# WPT_Round_2_1_RX_Schematics.net
KiCad netlist of a schematic drawn in Altium Designer
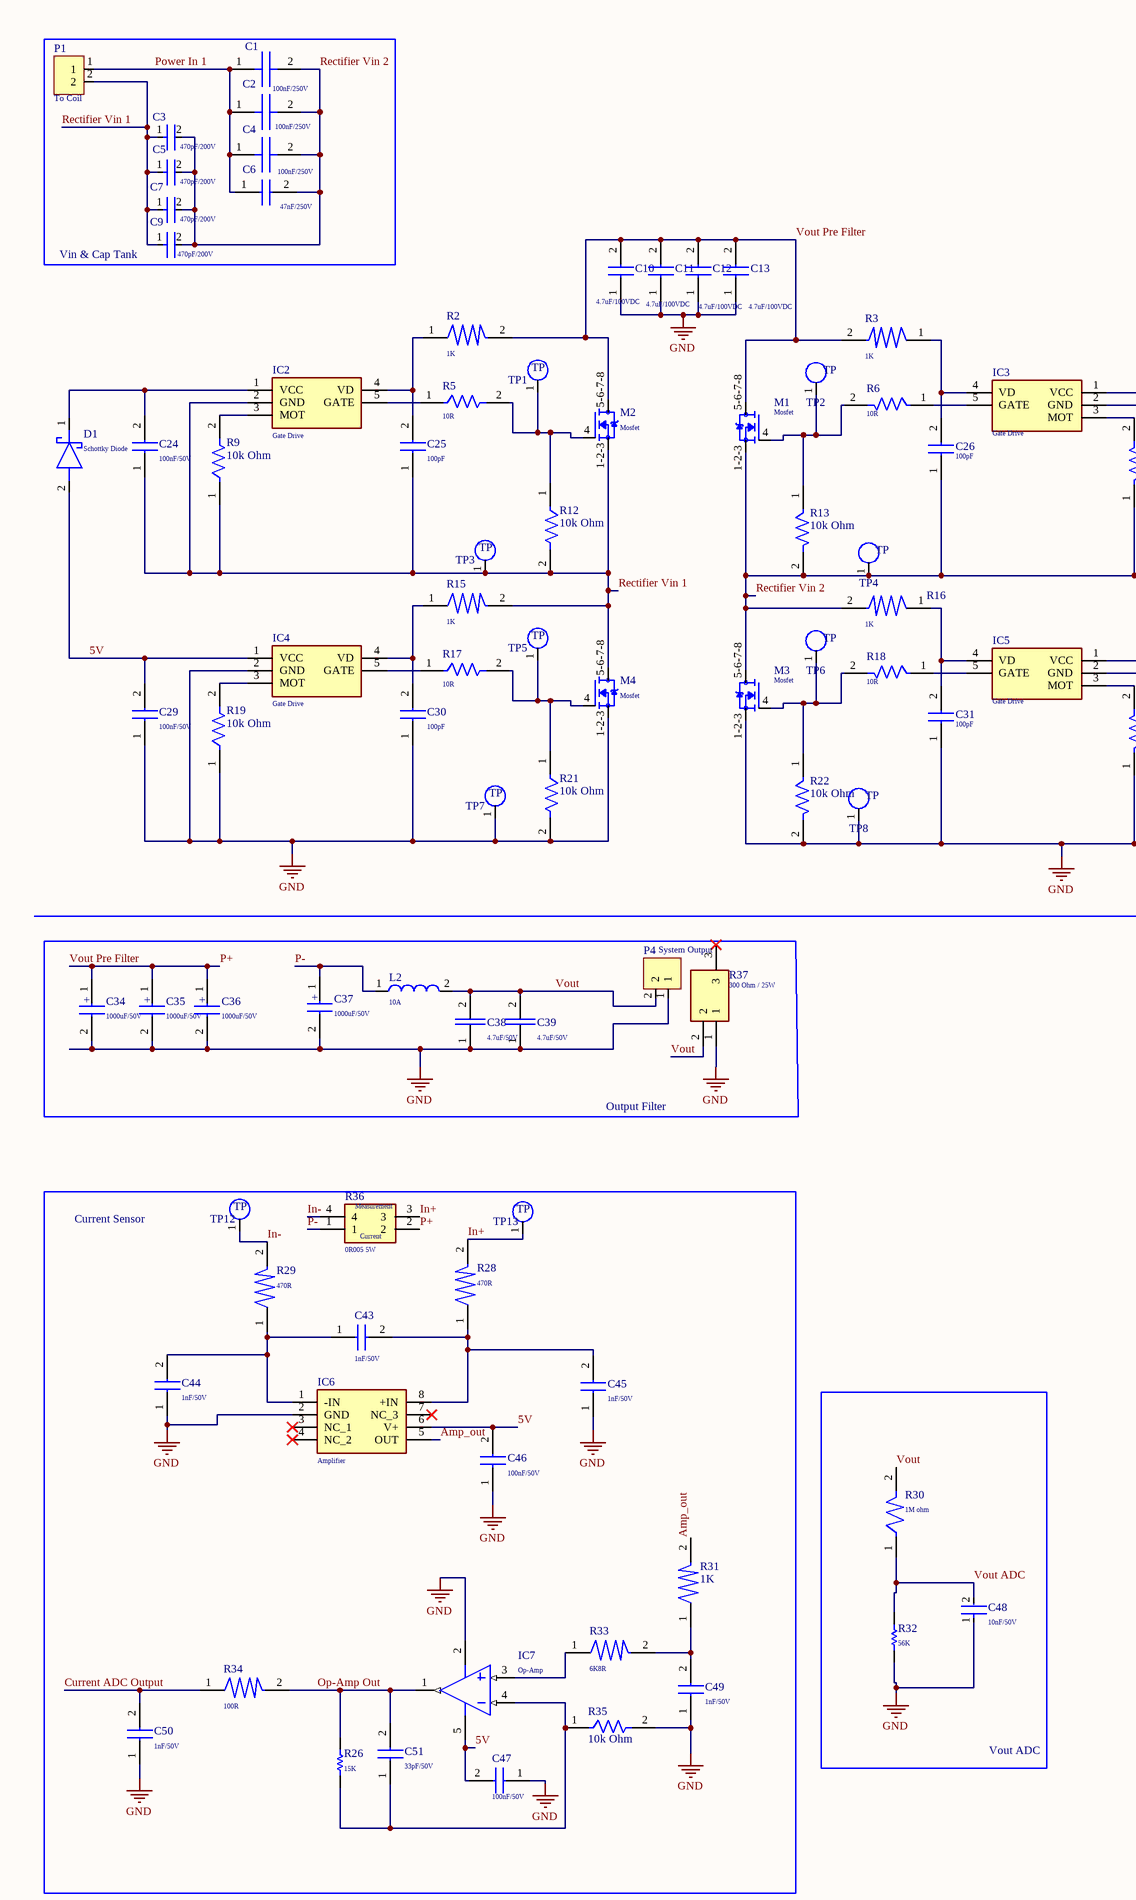
[diagram p0: WPT Round 2.1 RX Schematics.SchDoc, left]
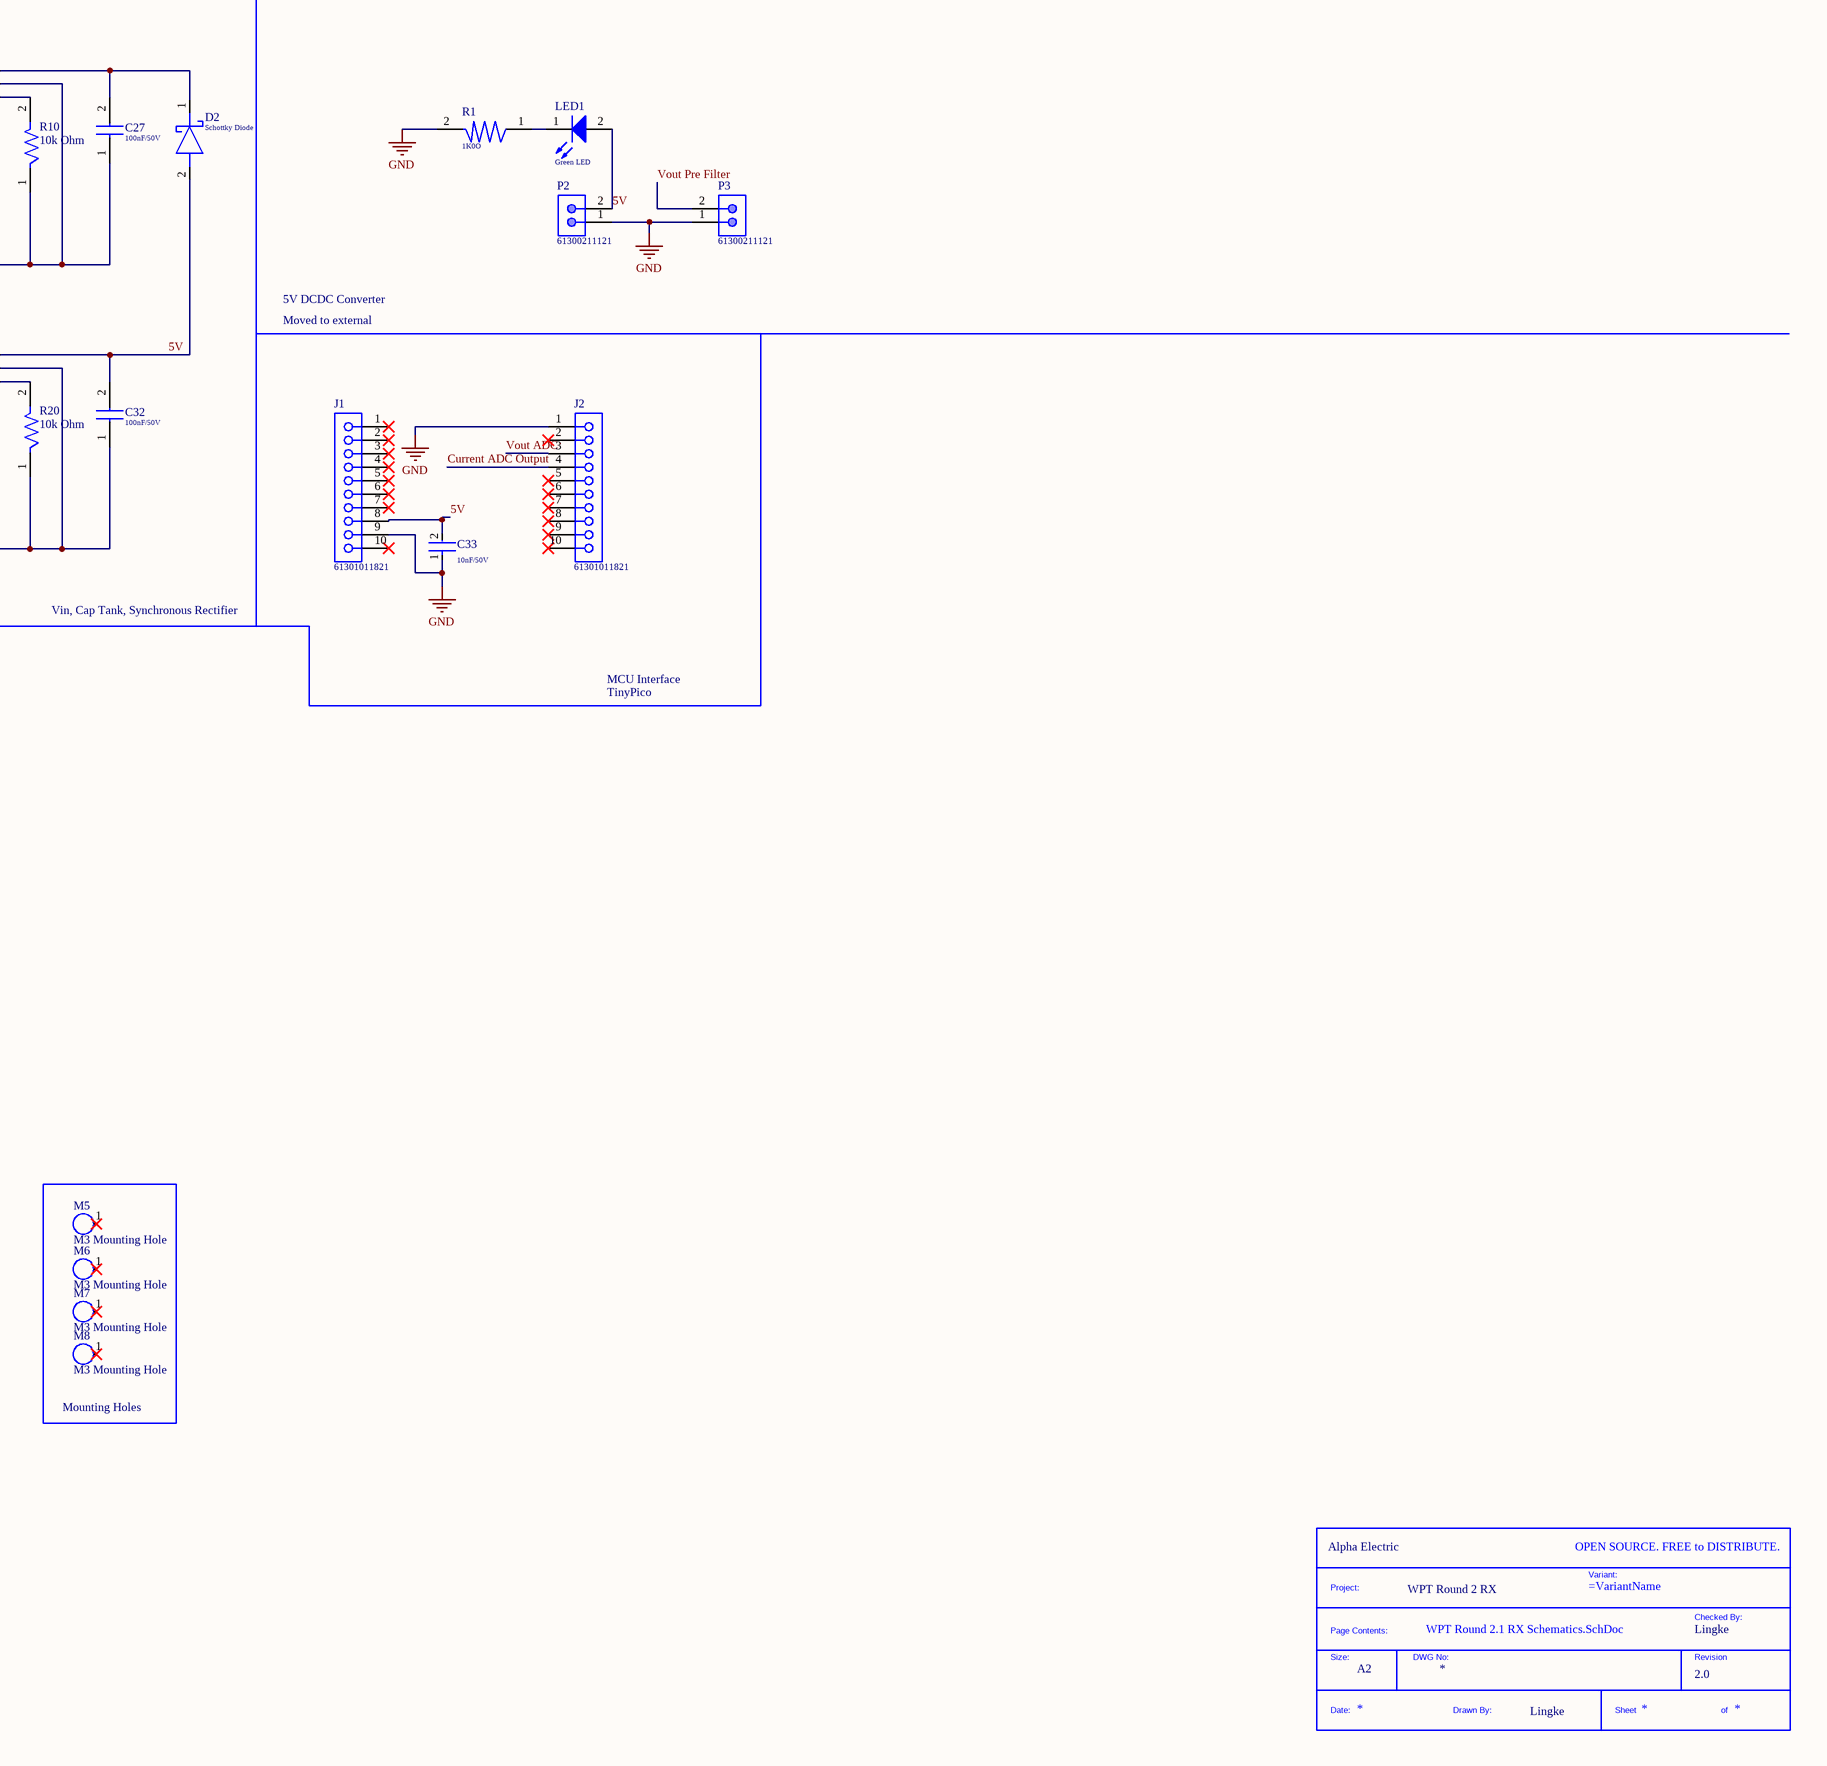
[diagram p1: WPT Round 2.1 RX Schematics.SchDoc, right]

(export (version "E")
  (design (tool "Eeschema 10.0.6"))
  (components
    (comp (ref "*")
      (value "Title_Block")
      (description "Standard Title Block.")
      (fields
        (field (name "PROJECT NAME") "WPT Round 2 RX")
        (field (name "COMPANY") "Alpha Electric")
        (field (name "DRAWN BY") "Lingke")
        (field (name "REVISION") "2.0")
        (field (name "DWG NO") "*")
        (field (name "SIZE") "A2")
        (field (name "CHECKED BY") "Lingke")
      )
      (libsource (lib "Symbol Library") (part "Title_Block"))
    )
    (comp (ref "C1")
      (value "100nF/250V")
      (footprint "SamacSys:CAPC4532X220N")
      (fields (field (name "MANUFACTURER_PART_NUMBER") "C1812C104JAGACAUTO"))
      (libsource (lib "Symbol Library") (part "C1812C104JAGACAUTO"))
    )
    (comp (ref "C2")
      (value "100nF/250V")
      (footprint "SamacSys:CAPC4532X220N")
      (fields (field (name "MANUFACTURER_PART_NUMBER") "C1812C104JAGACAUTO"))
      (libsource (lib "Symbol Library") (part "C1812C104JAGACAUTO"))
    )
    (comp (ref "C3")
      (value "470pF/200V")
      (footprint "FP-C1206C-EB-MFG")
      (description "CAP CER 470PF 200V 10% NP0 1206")
      (fields
        (field (name "OCTOPART") "https://octopart.com/c1206c471k2gactu-kemet-3658280")
        (field (name "TOLERANCE") "0.1")
      )
      (libsource (lib "Symbol Library") (part "C1206C471K2GACTU"))
    )
    (comp (ref "C4")
      (value "100nF/250V")
      (footprint "SamacSys:CAPC4532X220N")
      (fields (field (name "MANUFACTURER_PART_NUMBER") "C1812C104JAGACAUTO"))
      (libsource (lib "Symbol Library") (part "C1812C104JAGACAUTO"))
    )
    (comp (ref "C5")
      (value "470pF/200V")
      (footprint "FP-C1206C-EB-MFG")
      (description "CAP CER 470PF 200V 10% NP0 1206")
      (fields
        (field (name "OCTOPART") "https://octopart.com/c1206c471k2gactu-kemet-3658280")
        (field (name "TOLERANCE") "0.1")
      )
      (libsource (lib "Symbol Library") (part "C1206C471K2GACTU"))
    )
    (comp (ref "C6")
      (value "47nF/250V")
      (footprint "SamacSys:CAPC4532X350N")
      (description "Capacitor\r\n47nF/250V \r\nC0G")
      (fields (field (name "MANUFACTURER_PART_NUMBER") "C4532C0G2E473J320KA"))
      (libsource (lib "Symbol Library") (part "C4532C0G2E473J320KA"))
    )
    (comp (ref "C7")
      (value "470pF/200V")
      (footprint "FP-C1206C-EB-MFG")
      (description "CAP CER 470PF 200V 10% NP0 1206")
      (fields
        (field (name "OCTOPART") "https://octopart.com/c1206c471k2gactu-kemet-3658280")
        (field (name "TOLERANCE") "0.1")
      )
      (libsource (lib "Symbol Library") (part "C1206C471K2GACTU"))
    )
    (comp (ref "C9")
      (value "470pF/200V")
      (footprint "FP-C1206C-EB-MFG")
      (description "CAP CER 470PF 200V 10% NP0 1206")
      (fields
        (field (name "OCTOPART") "https://octopart.com/c1206c471k2gactu-kemet-3658280")
        (field (name "TOLERANCE") "0.1")
      )
      (libsource (lib "Symbol Library") (part "C1206C471K2GACTU"))
    )
    (comp (ref "C10")
      (value "4.7uF/100VDC")
      (footprint "SamacSys:CAPC3225X280N")
      (fields
        (field (name "MOUSER2 PART NUMBER") "810-CNC6P1X7R2A475K2")
        (field (name "MANUFACTURER_PART_NUMBER") "CNC6P1X7R2A475K250AE")
      )
      (libsource (lib "Symbol Library") (part "CNC6P1X7R2A475K250AE"))
    )
    (comp (ref "C11")
      (value "4.7uF/100VDC")
      (footprint "SamacSys:CAPC3225X280N")
      (fields
        (field (name "MOUSER2 PART NUMBER") "810-CNC6P1X7R2A475K2")
        (field (name "MANUFACTURER_PART_NUMBER") "CNC6P1X7R2A475K250AE")
      )
      (libsource (lib "Symbol Library") (part "CNC6P1X7R2A475K250AE"))
    )
    (comp (ref "C12")
      (value "4.7uF/100VDC")
      (footprint "SamacSys:CAPC3225X280N")
      (fields
        (field (name "MOUSER2 PART NUMBER") "810-CNC6P1X7R2A475K2")
        (field (name "MANUFACTURER_PART_NUMBER") "CNC6P1X7R2A475K250AE")
      )
      (libsource (lib "Symbol Library") (part "CNC6P1X7R2A475K250AE"))
    )
    (comp (ref "C13")
      (value "4.7uF/100VDC")
      (footprint "SamacSys:CAPC3225X280N")
      (fields
        (field (name "MOUSER2 PART NUMBER") "810-CNC6P1X7R2A475K2")
        (field (name "MANUFACTURER_PART_NUMBER") "CNC6P1X7R2A475K250AE")
      )
      (libsource (lib "Symbol Library") (part "CNC6P1X7R2A475K250AE"))
    )
    (comp (ref "C24")
      (value "100nF/50V")
      (footprint "SamacSys:CAPC2012X90N")
      (description "Capacitor 100nF/50V")
      (fields
        (field (name "MOUSER2 PART NUMBER") "710-885012207098")
        (field (name "MANUFACTURER_PART_NUMBER") "885012207098")
      )
      (libsource (lib "") (part "885012207098_1"))
    )
    (comp (ref "C25")
      (value "100pF")
      (footprint "SamacSys:CAPC2012X70N")
      (description "Capacitor 100pF")
      (fields (field (name "MANUFACTURER_PART_NUMBER") "885012007057"))
      (libsource (lib "") (part "885012007057_1"))
    )
    (comp (ref "C26")
      (value "100pF")
      (footprint "SamacSys:CAPC2012X70N")
      (description "Capacitor 100pF")
      (fields (field (name "MANUFACTURER_PART_NUMBER") "885012007057"))
      (libsource (lib "") (part "885012007057_1"))
    )
    (comp (ref "C27")
      (value "100nF/50V")
      (footprint "SamacSys:CAPC2012X90N")
      (description "Capacitor 100nF/50V")
      (fields
        (field (name "MOUSER2 PART NUMBER") "710-885012207098")
        (field (name "MANUFACTURER_PART_NUMBER") "885012207098")
      )
      (libsource (lib "") (part "885012207098_1"))
    )
    (comp (ref "C29")
      (value "100nF/50V")
      (footprint "SamacSys:CAPC2012X90N")
      (description "Capacitor 100nF/50V")
      (fields
        (field (name "MOUSER2 PART NUMBER") "710-885012207098")
        (field (name "MANUFACTURER_PART_NUMBER") "885012207098")
      )
      (libsource (lib "") (part "885012207098_2"))
    )
    (comp (ref "C30")
      (value "100pF")
      (footprint "SamacSys:CAPC2012X70N")
      (description "Capacitor 100pF")
      (fields (field (name "MANUFACTURER_PART_NUMBER") "885012007057"))
      (libsource (lib "Symbol Library") (part "885012007057"))
    )
    (comp (ref "C31")
      (value "100pF")
      (footprint "SamacSys:CAPC2012X70N")
      (description "Capacitor 100pF")
      (fields (field (name "MANUFACTURER_PART_NUMBER") "885012007057"))
      (libsource (lib "Symbol Library") (part "885012007057"))
    )
    (comp (ref "C32")
      (value "100nF/50V")
      (footprint "SamacSys:CAPC2012X90N")
      (description "Capacitor 100nF/50V")
      (fields
        (field (name "MOUSER2 PART NUMBER") "710-885012207098")
        (field (name "MANUFACTURER_PART_NUMBER") "885012207098")
      )
      (libsource (lib "") (part "885012207098_2"))
    )
    (comp (ref "C33")
      (value "10nF/50V")
      (footprint "0805 Capacitor")
      (libsource (lib "Symbol Library") (part "885012207092"))
    )
    (comp (ref "C34")
      (value "1000uF/50V")
      (footprint "SamacSys:CAPPRD500W62D1300H2650")
      (description "Capacitor 1000uF")
      (libsource (lib "Symbol Library") (part "ESH108M050AL4AA"))
    )
    (comp (ref "C35")
      (value "1000uF/50V")
      (footprint "SamacSys:CAPPRD500W62D1300H2650")
      (description "Capacitor 1000uF")
      (libsource (lib "Symbol Library") (part "ESH108M050AL4AA"))
    )
    (comp (ref "C36")
      (value "1000uF/50V")
      (footprint "SamacSys:CAPPRD500W62D1300H2650")
      (description "Capacitor 1000uF")
      (libsource (lib "Symbol Library") (part "ESH108M050AL4AA"))
    )
    (comp (ref "C37")
      (value "1000uF/50V")
      (footprint "SamacSys:CAPPRD500W62D1300H2650")
      (description "Capacitor 1000uF")
      (libsource (lib "Symbol Library") (part "ESH108M050AL4AA"))
    )
    (comp (ref "C38")
      (value "4.7uF/50V")
      (footprint "SamacSys:CAPC3225X280N")
      (description "Capacitor 4.7uF/50V")
      (fields (field (name "MANUFACTURER_PART_NUMBER") "885012209048"))
      (libsource (lib "Symbol Library") (part "885012209048"))
    )
    (comp (ref "C39")
      (value "4.7uF/50V")
      (footprint "SamacSys:CAPC3225X280N")
      (description "Capacitor 4.7uF/50V")
      (fields (field (name "MANUFACTURER_PART_NUMBER") "885012209048"))
      (libsource (lib "Symbol Library") (part "885012209048"))
    )
    (comp (ref "C43")
      (value "1nF/50V")
      (footprint "SamacSys:CAPC2012X90N")
      (fields (field (name "MANUFACTURER_PART_NUMBER") "885012207086"))
      (libsource (lib "Symbol Library") (part "885012207086"))
    )
    (comp (ref "C44")
      (value "1nF/50V")
      (footprint "SamacSys:CAPC2012X90N")
      (fields (field (name "MANUFACTURER_PART_NUMBER") "885012207086"))
      (libsource (lib "Symbol Library") (part "885012207086"))
    )
    (comp (ref "C45")
      (value "1nF/50V")
      (footprint "SamacSys:CAPC2012X90N")
      (fields (field (name "MANUFACTURER_PART_NUMBER") "885012207086"))
      (libsource (lib "Symbol Library") (part "885012207086"))
    )
    (comp (ref "C46")
      (value "100nF/50V")
      (footprint "SamacSys:CAPC2012X90N")
      (libsource (lib "Symbol Library") (part "885012207098"))
    )
    (comp (ref "C47")
      (value "100nF/50V")
      (footprint "SamacSys:CAPC2012X90N")
      (libsource (lib "Symbol Library") (part "885012207098"))
    )
    (comp (ref "C48")
      (value "10nF/50V")
      (footprint "0805 Capacitor")
      (libsource (lib "Symbol Library") (part "885012207092"))
    )
    (comp (ref "C49")
      (value "1nF/50V")
      (footprint "SamacSys:CAPC2012X90N")
      (fields (field (name "MANUFACTURER_PART_NUMBER") "885012207086"))
      (libsource (lib "Symbol Library") (part "885012207086"))
    )
    (comp (ref "C50")
      (value "1nF/50V")
      (footprint "SamacSys:CAPC2012X90N")
      (fields (field (name "MANUFACTURER_PART_NUMBER") "885012207086"))
      (libsource (lib "Symbol Library") (part "885012207086"))
    )
    (comp (ref "C51")
      (value "33pF/50V")
      (footprint "CAPC2012X90N")
      (description "Capacitor 33pF/50V")
      (fields (field (name "MANUFACTURER_PART_NUMBER") "C0805C330J5GACTU"))
      (libsource (lib "Symbol Library") (part "C0805C330J5GACTU"))
    )
    (comp (ref "D1")
      (value "Schottky Diode")
      (footprint "SamacSys:RB400VAM50TR")
      (fields
        (field (name "MOUSER2 PART NUMBER") "755-RB400VAM-50TR")
        (field (name "MANUFACTURER_PART_NUMBER") "RB400VAM-50TR")
      )
      (libsource (lib "Symbol Library") (part "RB400VAM-50TR"))
    )
    (comp (ref "D2")
      (value "Schottky Diode")
      (footprint "SamacSys:RB400VAM50TR")
      (fields
        (field (name "MOUSER2 PART NUMBER") "755-RB400VAM-50TR")
        (field (name "MANUFACTURER_PART_NUMBER") "RB400VAM-50TR")
      )
      (libsource (lib "Symbol Library") (part "RB400VAM-50TR"))
    )
    (comp (ref "IC2")
      (value "Gate Drive")
      (footprint "SamacSys:SOT95P280X145-5N")
      (description "Gate Driver IC")
      (fields (field (name "MANUFACTURER_PART_NUMBER") "IR1161LTRPBF"))
      (libsource (lib "") (part "IR1161LTRPBF_1"))
    )
    (comp (ref "IC3")
      (value "Gate Drive")
      (footprint "SamacSys:SOT95P280X145-5N")
      (description "Gate Driver IC")
      (fields (field (name "MANUFACTURER_PART_NUMBER") "IR1161LTRPBF"))
      (libsource (lib "Symbol Library") (part "IR1161LTRPBF"))
    )
    (comp (ref "IC4")
      (value "Gate Drive")
      (footprint "SamacSys:SOT95P280X145-5N")
      (description "Gate Driver IC")
      (fields (field (name "MANUFACTURER_PART_NUMBER") "IR1161LTRPBF"))
      (libsource (lib "") (part "IR1161LTRPBF_1"))
    )
    (comp (ref "IC5")
      (value "Gate Drive")
      (footprint "SamacSys:SOT95P280X145-5N")
      (description "Gate Driver IC")
      (fields (field (name "MANUFACTURER_PART_NUMBER") "IR1161LTRPBF"))
      (libsource (lib "Symbol Library") (part "IR1161LTRPBF"))
    )
    (comp (ref "IC6")
      (value "Amplifier")
      (footprint "SamacSys:SOIC127P600X175-8N")
      (description "Integrated Circuit Amplifier")
      (fields (field (name "MANUFACTURER_PART_NUMBER") "AD8215YRZ"))
      (libsource (lib "Symbol Library") (part "AD8215YRZ"))
    )
    (comp (ref "IC7")
      (value "Op-Amp")
      (footprint "ADI-RJ-5_N")
      (fields
        (field (name "MANUFACTURER") "Analog Devices")
        (field (name "PARTNUMBER") "AD8031ARTZ-REEL7")
        (field (name "GENERIC PART NUMBER") "AD8031")
      )
      (libsource (lib "Symbol Library") (part "AD8031ARTZ-REEL7"))
    )
    (comp (ref "J1")
      (value "61301011821")
      (footprint "61301011821")
      (description "WR-PHD Socket Header, THT, pitch 2.54mm, Single Row, Vertical, 10p")
      (fields (field (name "MANUFACTURER") "Wurth Elektronik"))
      (libsource (lib "Altium_WR-PHD (rev20a)") (part "61301011821"))
    )
    (comp (ref "J2")
      (value "61301011821")
      (footprint "61301011821")
      (description "WR-PHD Socket Header, THT, pitch 2.54mm, Single Row, Vertical, 10p")
      (fields (field (name "MANUFACTURER") "Wurth Elektronik"))
      (libsource (lib "Altium_WR-PHD (rev20a)") (part "61301011821"))
    )
    (comp (ref "L2")
      (value "10A")
      (footprint "WE-PF_1280")
      (description "SMD EMI Suppression Power Ferrite WE-PF, Z = 2900 Ohm")
      (libsource (lib "Symbol Library") (part "742792901"))
    )
    (comp (ref "LED1")
      (value "Green LED")
      (footprint "0805_A")
      (description "SMD mono-color Chip LED, WL-SMCW, Green")
      (fields (field (name "PARTNUMBER") "150080GS75000") (field (name "MANUFACTURER") "Wuerth Elektronik"))
      (libsource (lib "Symbol Library") (part "150080GS75000"))
    )
    (comp (ref "M1")
      (value "Mosfet")
      (footprint "Footprint Library:TRANS_BSZ037N06LS5ATMA1")
      (fields (field (name "MP") "BSZ037N06LS5ATMA1") (field (name "MF") "Infineon Technologies"))
      (libsource (lib "Symbol Library") (part "BSZ070N08LS5ATMA1"))
    )
    (comp (ref "M2")
      (value "Mosfet")
      (footprint "Footprint Library:TRANS_BSZ037N06LS5ATMA1")
      (fields (field (name "MP") "BSZ037N06LS5ATMA1") (field (name "MF") "Infineon Technologies"))
      (libsource (lib "Symbol Library") (part "BSZ070N08LS5ATMA1"))
    )
    (comp (ref "M3")
      (value "Mosfet")
      (footprint "Footprint Library:TRANS_BSZ037N06LS5ATMA1")
      (fields (field (name "MP") "BSZ037N06LS5ATMA1") (field (name "MF") "Infineon Technologies"))
      (libsource (lib "Symbol Library") (part "BSZ070N08LS5ATMA1"))
    )
    (comp (ref "M4")
      (value "Mosfet")
      (footprint "Footprint Library:TRANS_BSZ037N06LS5ATMA1")
      (fields (field (name "MP") "BSZ037N06LS5ATMA1") (field (name "MF") "Infineon Technologies"))
      (libsource (lib "Symbol Library") (part "BSZ070N08LS5ATMA1"))
    )
    (comp (ref "M5")
      (value "M3 Mounting Hole")
      (footprint "M3 Hole")
      (libsource (lib "Symbol Library") (part "M3_Mounting_hole"))
    )
    (comp (ref "M6")
      (value "M3 Mounting Hole")
      (footprint "M3 Hole")
      (libsource (lib "Symbol Library") (part "M3_Mounting_hole"))
    )
    (comp (ref "M7")
      (value "M3 Mounting Hole")
      (footprint "M3 Hole")
      (libsource (lib "Symbol Library") (part "M3_Mounting_hole"))
    )
    (comp (ref "M8")
      (value "M3 Mounting Hole")
      (footprint "M3 Hole")
      (libsource (lib "Symbol Library") (part "M3_Mounting_hole"))
    )
    (comp (ref "P1")
      (value "To Coil")
      (footprint "691404910002B")
      (description "Serie 4049 B - 7.50mm Screwless Clamp Power Connector WR-TBL, 2 pin")
      (fields
        (field (name "PART NUMBER") "691404910002B")
        (field (name "MANUFACTURER") "Wurth Elektronik")
        (field (name "PUBLISHER") "WurthElektronik")
      )
      (libsource (lib "Symbol Library") (part "691404910002B"))
    )
    (comp (ref "P2")
      (value "61300211121")
      (footprint "61300211121")
      (description "WR-PHD Pin Header, THT, pitch 2.54mm, Single Row, Vertical, 2p")
      (fields (field (name "MANUFACTURER") "Wurth Elektronik"))
      (libsource (lib "Altium_WR-PHD (rev20a)") (part "61300211121"))
    )
    (comp (ref "P3")
      (value "61300211121")
      (footprint "61300211121")
      (description "WR-PHD Pin Header, THT, pitch 2.54mm, Single Row, Vertical, 2p")
      (fields (field (name "MANUFACTURER") "Wurth Elektronik"))
      (libsource (lib "Altium_WR-PHD (rev20a)") (part "61300211121"))
    )
    (comp (ref "P4")
      (value "System Output")
      (footprint "691404910002B")
      (description "Serie 4049 B - 7.50mm Screwless Clamp Power Connector WR-TBL, 2 pin")
      (fields
        (field (name "PART NUMBER") "691404910002B")
        (field (name "MANUFACTURER") "Wurth Elektronik")
        (field (name "PUBLISHER") "WurthElektronik")
      )
      (libsource (lib "") (part "691404910002B_1"))
    )
    (comp (ref "R1")
      (value "1K0O")
      (footprint "FP-CRCW0805-e3-MFG")
      (description "Resistor 1K0 Ohm")
      (libsource (lib "Symbol Library") (part "CRCW08051K00FKEAC"))
    )
    (comp (ref "R2")
      (value "1K")
      (footprint "FP-CRCW0805-e3-MFG")
      (description "Resistor 1k Ohm")
      (libsource (lib "Symbol Library") (part "CRCW08051K00FKEA"))
    )
    (comp (ref "R3")
      (value "1K")
      (footprint "FP-CRCW0805-e3-MFG")
      (description "Resistor 1k Ohm")
      (libsource (lib "Symbol Library") (part "CRCW08051K00FKEA"))
    )
    (comp (ref "R5")
      (value "10R")
      (footprint "FP-CRCW1206-e3-IPC_A")
      (description "RES Thick Film, 10Ω, 1%, 0.25W, 100ppm/°C, 1206\r\nMOSFET Gate Resistor 10Ohm")
      (fields (field (name "TOLERANCE") "1%"))
      (libsource (lib "Symbol Library") (part "CRCW120610R0FKEA"))
    )
    (comp (ref "R6")
      (value "10R")
      (footprint "FP-CRCW1206-e3-IPC_A")
      (description "RES Thick Film, 10Ω, 1%, 0.25W, 100ppm/°C, 1206\r\nMOSFET Gate Resistor 10Ohm")
      (fields (field (name "TOLERANCE") "1%"))
      (libsource (lib "Symbol Library") (part "CRCW120610R0FKEA"))
    )
    (comp (ref "R9")
      (value "10k Ohm")
      (footprint "0805 Resistor")
      (description "RES Thick Film, 10kΩ, 1%, 0.125W, 100ppm/°C, 0805\r\n10k Ohm")
      (fields (field (name "TOLERANCE") "1%"))
      (libsource (lib "Symbol Library") (part "CRCW080510K0FKEA"))
    )
    (comp (ref "R10")
      (value "10k Ohm")
      (footprint "0805 Resistor")
      (description "RES Thick Film, 10kΩ, 1%, 0.125W, 100ppm/°C, 0805\r\n10k Ohm")
      (fields (field (name "TOLERANCE") "1%"))
      (libsource (lib "Symbol Library") (part "CRCW080510K0FKEA"))
    )
    (comp (ref "R12")
      (value "10k Ohm")
      (footprint "0805 Resistor")
      (description "RES Thick Film, 10kΩ, 1%, 0.125W, 100ppm/°C, 0805\r\n10k Ohm")
      (fields (field (name "TOLERANCE") "1%"))
      (libsource (lib "Symbol Library") (part "CRCW080510K0FKEA"))
    )
    (comp (ref "R13")
      (value "10k Ohm")
      (footprint "0805 Resistor")
      (description "RES Thick Film, 10kΩ, 1%, 0.125W, 100ppm/°C, 0805\r\n10k Ohm")
      (fields (field (name "TOLERANCE") "1%"))
      (libsource (lib "Symbol Library") (part "CRCW080510K0FKEA"))
    )
    (comp (ref "R15")
      (value "1K")
      (footprint "FP-CRCW0805-e3-MFG")
      (description "Resistor 1k Ohm")
      (libsource (lib "Symbol Library") (part "CRCW08051K00FKEA"))
    )
    (comp (ref "R16")
      (value "1K")
      (footprint "FP-CRCW0805-e3-MFG")
      (description "Resistor 1k Ohm")
      (libsource (lib "Symbol Library") (part "CRCW08051K00FKEA"))
    )
    (comp (ref "R17")
      (value "10R")
      (footprint "FP-CRCW1206-e3-IPC_A")
      (description "RES Thick Film, 10Ω, 1%, 0.25W, 100ppm/°C, 1206\r\nMOSFET Gate Resistor 10Ohm")
      (fields (field (name "TOLERANCE") "1%"))
      (libsource (lib "Symbol Library") (part "CRCW120610R0FKEA"))
    )
    (comp (ref "R18")
      (value "10R")
      (footprint "FP-CRCW1206-e3-IPC_A")
      (description "RES Thick Film, 10Ω, 1%, 0.25W, 100ppm/°C, 1206\r\nMOSFET Gate Resistor 10Ohm")
      (fields (field (name "TOLERANCE") "1%"))
      (libsource (lib "Symbol Library") (part "CRCW120610R0FKEA"))
    )
    (comp (ref "R19")
      (value "10k Ohm")
      (footprint "0805 Resistor")
      (description "RES Thick Film, 10kΩ, 1%, 0.125W, 100ppm/°C, 0805\r\n10k Ohm")
      (fields (field (name "TOLERANCE") "1%"))
      (libsource (lib "") (part "CRCW080510K0FKEA_1"))
    )
    (comp (ref "R20")
      (value "10k Ohm")
      (footprint "0805 Resistor")
      (description "RES Thick Film, 10kΩ, 1%, 0.125W, 100ppm/°C, 0805\r\n10k Ohm")
      (fields (field (name "TOLERANCE") "1%"))
      (libsource (lib "") (part "CRCW080510K0FKEA_1"))
    )
    (comp (ref "R21")
      (value "10k Ohm")
      (footprint "0805 Resistor")
      (description "RES Thick Film, 10kΩ, 1%, 0.125W, 100ppm/°C, 0805\r\n10k Ohm")
      (fields (field (name "TOLERANCE") "1%"))
      (libsource (lib "Symbol Library") (part "CRCW080510K0FKEA"))
    )
    (comp (ref "R22")
      (value "10k Ohm")
      (footprint "0805 Resistor")
      (description "RES Thick Film, 10kΩ, 1%, 0.125W, 100ppm/°C, 0805\r\n10k Ohm")
      (fields (field (name "TOLERANCE") "1%"))
      (libsource (lib "Symbol Library") (part "CRCW080510K0FKEA"))
    )
    (comp (ref "R26")
      (value "15K")
      (footprint "0805 Resistor")
      (description "15K Ohm Resistor")
      (libsource (lib "Symbol Library") (part "ERA-6AED153V"))
    )
    (comp (ref "R28")
      (value "470R")
      (footprint "FP-CRCW0805-e3-MFG")
      (description "Resistor 470 Ohm")
      (libsource (lib "Symbol Library") (part "CRCW0805470RFKEB"))
    )
    (comp (ref "R29")
      (value "470R")
      (footprint "FP-CRCW0805-e3-MFG")
      (description "Resistor 470 Ohm")
      (libsource (lib "Symbol Library") (part "CRCW0805470RFKEB"))
    )
    (comp (ref "R30")
      (value "1M ohm")
      (footprint "FP-CRCW0805-e3-MFG")
      (description "RES Thick Film, 1MΩ, 1%, 0.125W, 100ppm/°C, 0805\r\n1M Ohm Resistor")
      (fields (field (name "TOLERANCE") "1%"))
      (libsource (lib "Symbol Library") (part "CRCW08051M00FKEA"))
    )
    (comp (ref "R31")
      (value "1K")
      (footprint "FP-CRCW0805-e3-MFG")
      (description "Resistor 1k Ohm")
      (libsource (lib "Symbol Library") (part "CRCW08051K00FKEA"))
    )
    (comp (ref "R32")
      (value "56K")
      (footprint "0805 Resistor")
      (description "56K Ohm Resistor")
      (libsource (lib "Symbol Library") (part "ERJ-6ENF5622V"))
    )
    (comp (ref "R33")
      (value "6K8R")
      (footprint "FP-CRCW0805-e3-MFG")
      (description "Resistor 6.8K Ohm")
      (libsource (lib "Symbol Library") (part "CRCW08056K80FKEA"))
    )
    (comp (ref "R34")
      (value "100R")
      (footprint "FP-CRCW0805-e3-MFG")
      (description "Resistor 100 Ohm")
      (libsource (lib "Symbol Library") (part "CRCW0805100RFKEB"))
    )
    (comp (ref "R35")
      (value "10k Ohm")
      (footprint "0805 Resistor")
      (description "RES Thick Film, 10kΩ, 1%, 0.125W, 100ppm/°C, 0805\r\n10k Ohm")
      (fields (field (name "TOLERANCE") "1%"))
      (libsource (lib "Symbol Library") (part "CRCW080510K0FKEA"))
    )
    (comp (ref "R36")
      (value "0R005 5W")
      (footprint "SamacSys:FC4L110R005FER")
      (description "Resistor 0R005 5W")
      (fields (field (name "MANUFACTURER_PART_NUMBER") "FC4L110R005FER"))
      (libsource (lib "Symbol Library") (part "FC4L110R005FER"))
    )
    (comp (ref "R37")
      (value "300 Ohm / 25W")
      (footprint "SamacSys:PWR163S253000FE")
      (description "Resistor 300 Ohm / 25W")
      (fields (field (name "MANUFACTURER_PART_NUMBER") "PWR163S-25-3000FE"))
      (libsource (lib "Symbol Library") (part "PWR163S-25-3000FE"))
    )
    (comp (ref "TP1")
      (value "TP")
      (footprint "Test Point")
      (description "Test Point 1mm by 1mm")
      (libsource (lib "Symbol Library") (part "Test Point"))
    )
    (comp (ref "TP2")
      (value "TP")
      (footprint "Test Point")
      (description "Test Point 1mm by 1mm")
      (libsource (lib "Symbol Library") (part "Test Point"))
    )
    (comp (ref "TP3")
      (value "TP")
      (footprint "Test Point")
      (description "Test Point 1mm by 1mm")
      (libsource (lib "Symbol Library") (part "Test Point"))
    )
    (comp (ref "TP4")
      (value "TP")
      (footprint "Test Point")
      (description "Test Point 1mm by 1mm")
      (libsource (lib "Symbol Library") (part "Test Point"))
    )
    (comp (ref "TP5")
      (value "TP")
      (footprint "Test Point")
      (description "Test Point 1mm by 1mm")
      (libsource (lib "Symbol Library") (part "Test Point"))
    )
    (comp (ref "TP6")
      (value "TP")
      (footprint "Test Point")
      (description "Test Point 1mm by 1mm")
      (libsource (lib "Symbol Library") (part "Test Point"))
    )
    (comp (ref "TP7")
      (value "TP")
      (footprint "Test Point")
      (description "Test Point 1mm by 1mm")
      (libsource (lib "Symbol Library") (part "Test Point"))
    )
    (comp (ref "TP8")
      (value "TP")
      (footprint "Test Point")
      (description "Test Point 1mm by 1mm")
      (libsource (lib "Symbol Library") (part "Test Point"))
    )
    (comp (ref "TP12")
      (value "TP")
      (footprint "Test Point")
      (description "Test Point 1mm by 1mm")
      (libsource (lib "Symbol Library") (part "Test Point"))
    )
    (comp (ref "TP13")
      (value "TP")
      (footprint "Test Point")
      (description "Test Point 1mm by 1mm")
      (libsource (lib "Symbol Library") (part "Test Point"))
    )
  )
  (nets
    (net (code "1") (name "/5V") (class "Default")
      (node (ref "C29") (pin "2") (pinfunction "2_2") (pintype "passive"))
      (node (ref "C32") (pin "2") (pinfunction "2_2") (pintype "passive"))
      (node (ref "C33") (pin "2") (pinfunction "2_2") (pintype "passive"))
      (node (ref "C46") (pin "2") (pinfunction "2_2") (pintype "passive"))
      (node (ref "C47") (pin "2") (pinfunction "2_2") (pintype "passive"))
      (node (ref "D1") (pin "2") (pinfunction "A_2") (pintype "passive"))
      (node (ref "D2") (pin "2") (pinfunction "A_2") (pintype "passive"))
      (node (ref "IC4") (pin "1") (pinfunction "VCC_1") (pintype "passive"))
      (node (ref "IC5") (pin "1") (pinfunction "VCC_1") (pintype "passive"))
      (node (ref "IC6") (pin "6") (pinfunction "V+_6") (pintype "passive"))
      (node (ref "IC7") (pin "5") (pinfunction "+VS_5") (pintype "power_in"))
      (node (ref "J1") (pin "8") (pinfunction "8_8") (pintype "passive"))
      (node (ref "LED1") (pin "2") (pinfunction "A_2") (pintype "passive"))
      (node (ref "P2") (pin "2") (pinfunction "2_2") (pintype "passive"))
    )
    (net (code "2") (name "/Amp_out") (class "Default")
      (node (ref "IC6") (pin "5") (pinfunction "OUT_5") (pintype "passive"))
      (node (ref "R31") (pin "2") (pinfunction "2_2") (pintype "passive"))
    )
    (net (code "3") (name "/Current ADC Output") (class "Default")
      (node (ref "C50") (pin "2") (pinfunction "2_2") (pintype "passive"))
      (node (ref "J2") (pin "4") (pinfunction "4_4") (pintype "passive"))
      (node (ref "R34") (pin "1") (pinfunction "1_1") (pintype "passive"))
    )
    (net (code "4") (name "/In+") (class "Default")
      (node (ref "R28") (pin "2") (pinfunction "2_2") (pintype "passive"))
      (node (ref "R36") (pin "3") (pinfunction "3_3") (pintype "passive"))
      (node (ref "TP13") (pin "1") (pinfunction "TP_1") (pintype "passive"))
    )
    (net (code "5") (name "/In-") (class "Default")
      (node (ref "R29") (pin "2") (pinfunction "2_2") (pintype "passive"))
      (node (ref "R36") (pin "4") (pinfunction "4_4") (pintype "passive"))
      (node (ref "TP12") (pin "1") (pinfunction "TP_1") (pintype "passive"))
    )
    (net (code "6") (name "/Op-Amp Out") (class "Default")
      (node (ref "C51") (pin "2") (pinfunction "C2_2") (pintype "passive"))
      (node (ref "IC7") (pin "1") (pinfunction "VOUT_1") (pintype "output"))
      (node (ref "R26") (pin "2") (pinfunction "2_2") (pintype "passive"))
      (node (ref "R34") (pin "2") (pinfunction "2_2") (pintype "passive"))
    )
    (net (code "7") (name "/P+") (class "Default")
      (node (ref "C10") (pin "2") (pinfunction "2_2") (pintype "passive"))
      (node (ref "C11") (pin "2") (pinfunction "2_2") (pintype "passive"))
      (node (ref "C12") (pin "2") (pinfunction "2_2") (pintype "passive"))
      (node (ref "C13") (pin "2") (pinfunction "2_2") (pintype "passive"))
      (node (ref "C34") (pin "1") (pinfunction "+_1") (pintype "passive"))
      (node (ref "C35") (pin "1") (pinfunction "+_1") (pintype "passive"))
      (node (ref "C36") (pin "1") (pinfunction "+_1") (pintype "passive"))
      (node (ref "M1") (pin "5-6-7-8") (pinfunction "D_5-6-7-8") (pintype "passive"))
      (node (ref "M2") (pin "5-6-7-8") (pinfunction "D_5-6-7-8") (pintype "passive"))
      (node (ref "P3") (pin "2") (pinfunction "2_2") (pintype "passive"))
      (node (ref "R2") (pin "2") (pinfunction "2_2") (pintype "passive"))
      (node (ref "R3") (pin "2") (pinfunction "2_2") (pintype "passive"))
      (node (ref "R36") (pin "2") (pinfunction "2_2") (pintype "passive"))
    )
    (net (code "8") (name "/P-") (class "Default")
      (node (ref "C37") (pin "1") (pinfunction "+_1") (pintype "passive"))
      (node (ref "L2") (pin "1") (pinfunction "1_1") (pintype "passive"))
      (node (ref "R36") (pin "1") (pinfunction "1_1") (pintype "passive"))
    )
    (net (code "9") (name "/Power In 1") (class "Default")
      (node (ref "C1") (pin "1") (pinfunction "1_1") (pintype "passive"))
      (node (ref "C2") (pin "1") (pinfunction "1_1") (pintype "passive"))
      (node (ref "C4") (pin "1") (pinfunction "1_1") (pintype "passive"))
      (node (ref "C6") (pin "1") (pinfunction "1_1") (pintype "passive"))
      (node (ref "P1") (pin "1") (pinfunction "1_1") (pintype "passive"))
    )
    (net (code "10") (name "/Rectifier Vin 1") (class "Default")
      (node (ref "C24") (pin "1") (pinfunction "1_1") (pintype "passive"))
      (node (ref "C25") (pin "1") (pinfunction "1_1") (pintype "passive"))
      (node (ref "C3") (pin "1") (pinfunction "1_1") (pintype "passive"))
      (node (ref "C5") (pin "1") (pinfunction "1_1") (pintype "passive"))
      (node (ref "C7") (pin "1") (pinfunction "1_1") (pintype "passive"))
      (node (ref "C9") (pin "1") (pinfunction "1_1") (pintype "passive"))
      (node (ref "IC2") (pin "2") (pinfunction "GND_2") (pintype "passive"))
      (node (ref "M2") (pin "1-2-3") (pinfunction "S_1-2-3") (pintype "passive"))
      (node (ref "M4") (pin "5-6-7-8") (pinfunction "D_5-6-7-8") (pintype "passive"))
      (node (ref "P1") (pin "2") (pinfunction "2_2") (pintype "passive"))
      (node (ref "R12") (pin "2") (pinfunction "2_2") (pintype "passive"))
      (node (ref "R15") (pin "2") (pinfunction "2_2") (pintype "passive"))
      (node (ref "R9") (pin "1") (pinfunction "1_1") (pintype "passive"))
      (node (ref "TP3") (pin "1") (pinfunction "TP_1") (pintype "passive"))
    )
    (net (code "11") (name "/Rectifier Vin 2") (class "Default")
      (node (ref "C1") (pin "2") (pinfunction "2_2") (pintype "passive"))
      (node (ref "C2") (pin "2") (pinfunction "2_2") (pintype "passive"))
      (node (ref "C26") (pin "1") (pinfunction "1_1") (pintype "passive"))
      (node (ref "C27") (pin "1") (pinfunction "1_1") (pintype "passive"))
      (node (ref "C3") (pin "2") (pinfunction "2_2") (pintype "passive"))
      (node (ref "C4") (pin "2") (pinfunction "2_2") (pintype "passive"))
      (node (ref "C5") (pin "2") (pinfunction "2_2") (pintype "passive"))
      (node (ref "C6") (pin "2") (pinfunction "2_2") (pintype "passive"))
      (node (ref "C7") (pin "2") (pinfunction "2_2") (pintype "passive"))
      (node (ref "C9") (pin "2") (pinfunction "2_2") (pintype "passive"))
      (node (ref "IC3") (pin "2") (pinfunction "GND_2") (pintype "passive"))
      (node (ref "M1") (pin "1-2-3") (pinfunction "S_1-2-3") (pintype "passive"))
      (node (ref "M3") (pin "5-6-7-8") (pinfunction "D_5-6-7-8") (pintype "passive"))
      (node (ref "R10") (pin "1") (pinfunction "1_1") (pintype "passive"))
      (node (ref "R13") (pin "2") (pinfunction "2_2") (pintype "passive"))
      (node (ref "R16") (pin "2") (pinfunction "2_2") (pintype "passive"))
      (node (ref "TP4") (pin "1") (pinfunction "TP_1") (pintype "passive"))
    )
    (net (code "12") (name "/Vout") (class "Default")
      (node (ref "C38") (pin "2") (pinfunction "2_2") (pintype "passive"))
      (node (ref "C39") (pin "2") (pinfunction "2_2") (pintype "passive"))
      (node (ref "L2") (pin "2") (pinfunction "2_2") (pintype "passive"))
      (node (ref "P4") (pin "2") (pinfunction "2_2") (pintype "passive"))
      (node (ref "R30") (pin "2") (pinfunction "2_2") (pintype "passive"))
      (node (ref "R37") (pin "2") (pinfunction "2_2") (pintype "passive"))
    )
    (net (code "13") (name "/Vout ADC") (class "Default")
      (node (ref "C48") (pin "2") (pinfunction "2_2") (pintype "passive"))
      (node (ref "J2") (pin "3") (pinfunction "3_3") (pintype "passive"))
      (node (ref "R30") (pin "1") (pinfunction "1_1") (pintype "passive"))
      (node (ref "R32") (pin "2") (pinfunction "2_2") (pintype "passive"))
    )
    (net (code "14") (name "GND") (class "Default")
      (node (ref "C10") (pin "1") (pinfunction "1_1") (pintype "passive"))
      (node (ref "C11") (pin "1") (pinfunction "1_1") (pintype "passive"))
      (node (ref "C12") (pin "1") (pinfunction "1_1") (pintype "passive"))
      (node (ref "C13") (pin "1") (pinfunction "1_1") (pintype "passive"))
      (node (ref "C29") (pin "1") (pinfunction "1_1") (pintype "passive"))
      (node (ref "C30") (pin "1") (pinfunction "1_1") (pintype "passive"))
      (node (ref "C31") (pin "1") (pinfunction "1_1") (pintype "passive"))
      (node (ref "C32") (pin "1") (pinfunction "1_1") (pintype "passive"))
      (node (ref "C33") (pin "1") (pinfunction "1_1") (pintype "passive"))
      (node (ref "C34") (pin "2") (pinfunction "-_2") (pintype "passive"))
      (node (ref "C35") (pin "2") (pinfunction "-_2") (pintype "passive"))
      (node (ref "C36") (pin "2") (pinfunction "-_2") (pintype "passive"))
      (node (ref "C37") (pin "2") (pinfunction "-_2") (pintype "passive"))
      (node (ref "C38") (pin "1") (pinfunction "1_1") (pintype "passive"))
      (node (ref "C39") (pin "1") (pinfunction "1_1") (pintype "passive"))
      (node (ref "C44") (pin "1") (pinfunction "1_1") (pintype "passive"))
      (node (ref "C45") (pin "1") (pinfunction "1_1") (pintype "passive"))
      (node (ref "C46") (pin "1") (pinfunction "1_1") (pintype "passive"))
      (node (ref "C47") (pin "1") (pinfunction "1_1") (pintype "passive"))
      (node (ref "C48") (pin "1") (pinfunction "1_1") (pintype "passive"))
      (node (ref "C49") (pin "1") (pinfunction "1_1") (pintype "passive"))
      (node (ref "C50") (pin "1") (pinfunction "1_1") (pintype "passive"))
      (node (ref "IC4") (pin "2") (pinfunction "GND_2") (pintype "passive"))
      (node (ref "IC5") (pin "2") (pinfunction "GND_2") (pintype "passive"))
      (node (ref "IC6") (pin "2") (pinfunction "GND_2") (pintype "passive"))
      (node (ref "IC7") (pin "2") (pinfunction "-VS_2") (pintype "power_in"))
      (node (ref "J1") (pin "9") (pinfunction "9_9") (pintype "passive"))
      (node (ref "J2") (pin "1") (pinfunction "1_1") (pintype "passive"))
      (node (ref "M3") (pin "1-2-3") (pinfunction "S_1-2-3") (pintype "passive"))
      (node (ref "M4") (pin "1-2-3") (pinfunction "S_1-2-3") (pintype "passive"))
      (node (ref "P2") (pin "1") (pinfunction "1_1") (pintype "passive"))
      (node (ref "P3") (pin "1") (pinfunction "1_1") (pintype "passive"))
      (node (ref "P4") (pin "1") (pinfunction "1_1") (pintype "passive"))
      (node (ref "R1") (pin "2") (pinfunction "2_2") (pintype "passive"))
      (node (ref "R19") (pin "1") (pinfunction "1_1") (pintype "passive"))
      (node (ref "R20") (pin "1") (pinfunction "1_1") (pintype "passive"))
      (node (ref "R21") (pin "2") (pinfunction "2_2") (pintype "passive"))
      (node (ref "R22") (pin "2") (pinfunction "2_2") (pintype "passive"))
      (node (ref "R32") (pin "1") (pinfunction "1_1") (pintype "passive"))
      (node (ref "R35") (pin "2") (pinfunction "2_2") (pintype "passive"))
      (node (ref "R37") (pin "1") (pinfunction "1_1") (pintype "passive"))
      (node (ref "TP7") (pin "1") (pinfunction "TP_1") (pintype "passive"))
      (node (ref "TP8") (pin "1") (pinfunction "TP_1") (pintype "passive"))
    )
    (net (code "15") (name "Net-(C49-Pad2)") (class "Default")
      (node (ref "C49") (pin "2") (pinfunction "2_2") (pintype "passive"))
      (node (ref "R31") (pin "1") (pinfunction "1_1") (pintype "passive"))
      (node (ref "R33") (pin "2") (pinfunction "2_2") (pintype "passive"))
    )
    (net (code "16") (name "Net-(C51-C1)") (class "Default")
      (node (ref "C51") (pin "1") (pinfunction "C1_1") (pintype "passive"))
      (node (ref "IC7") (pin "4") (pinfunction "-IN_4") (pintype "input"))
      (node (ref "R26") (pin "1") (pinfunction "1_1") (pintype "passive"))
      (node (ref "R35") (pin "1") (pinfunction "1_1") (pintype "passive"))
    )
    (net (code "17") (name "Net-(D1-K)") (class "Default")
      (node (ref "C24") (pin "2") (pinfunction "2_2") (pintype "passive"))
      (node (ref "D1") (pin "1") (pinfunction "K_1") (pintype "passive"))
      (node (ref "IC2") (pin "1") (pinfunction "VCC_1") (pintype "passive"))
    )
    (net (code "18") (name "Net-(D2-K)") (class "Default")
      (node (ref "C27") (pin "2") (pinfunction "2_2") (pintype "passive"))
      (node (ref "D2") (pin "1") (pinfunction "K_1") (pintype "passive"))
      (node (ref "IC3") (pin "1") (pinfunction "VCC_1") (pintype "passive"))
    )
    (net (code "19") (name "Net-(IC2-GATE)") (class "Default")
      (node (ref "IC2") (pin "5") (pinfunction "GATE_5") (pintype "passive"))
      (node (ref "R5") (pin "1") (pinfunction "1_1") (pintype "passive"))
    )
    (net (code "20") (name "Net-(IC2-MOT)") (class "Default")
      (node (ref "IC2") (pin "3") (pinfunction "MOT_3") (pintype "passive"))
      (node (ref "R9") (pin "2") (pinfunction "2_2") (pintype "passive"))
    )
    (net (code "21") (name "Net-(IC2-VD)") (class "Default")
      (node (ref "C25") (pin "2") (pinfunction "2_2") (pintype "passive"))
      (node (ref "IC2") (pin "4") (pinfunction "VD_4") (pintype "passive"))
      (node (ref "R2") (pin "1") (pinfunction "1_1") (pintype "passive"))
    )
    (net (code "22") (name "Net-(IC3-GATE)") (class "Default")
      (node (ref "IC3") (pin "5") (pinfunction "GATE_5") (pintype "passive"))
      (node (ref "R6") (pin "1") (pinfunction "1_1") (pintype "passive"))
    )
    (net (code "23") (name "Net-(IC3-MOT)") (class "Default")
      (node (ref "IC3") (pin "3") (pinfunction "MOT_3") (pintype "passive"))
      (node (ref "R10") (pin "2") (pinfunction "2_2") (pintype "passive"))
    )
    (net (code "24") (name "Net-(IC3-VD)") (class "Default")
      (node (ref "C26") (pin "2") (pinfunction "2_2") (pintype "passive"))
      (node (ref "IC3") (pin "4") (pinfunction "VD_4") (pintype "passive"))
      (node (ref "R3") (pin "1") (pinfunction "1_1") (pintype "passive"))
    )
    (net (code "25") (name "Net-(IC4-GATE)") (class "Default")
      (node (ref "IC4") (pin "5") (pinfunction "GATE_5") (pintype "passive"))
      (node (ref "R17") (pin "1") (pinfunction "1_1") (pintype "passive"))
    )
    (net (code "26") (name "Net-(IC4-MOT)") (class "Default")
      (node (ref "IC4") (pin "3") (pinfunction "MOT_3") (pintype "passive"))
      (node (ref "R19") (pin "2") (pinfunction "2_2") (pintype "passive"))
    )
    (net (code "27") (name "Net-(IC4-VD)") (class "Default")
      (node (ref "C30") (pin "2") (pinfunction "2_2") (pintype "passive"))
      (node (ref "IC4") (pin "4") (pinfunction "VD_4") (pintype "passive"))
      (node (ref "R15") (pin "1") (pinfunction "1_1") (pintype "passive"))
    )
    (net (code "28") (name "Net-(IC5-GATE)") (class "Default")
      (node (ref "IC5") (pin "5") (pinfunction "GATE_5") (pintype "passive"))
      (node (ref "R18") (pin "1") (pinfunction "1_1") (pintype "passive"))
    )
    (net (code "29") (name "Net-(IC5-MOT)") (class "Default")
      (node (ref "IC5") (pin "3") (pinfunction "MOT_3") (pintype "passive"))
      (node (ref "R20") (pin "2") (pinfunction "2_2") (pintype "passive"))
    )
    (net (code "30") (name "Net-(IC5-VD)") (class "Default")
      (node (ref "C31") (pin "2") (pinfunction "2_2") (pintype "passive"))
      (node (ref "IC5") (pin "4") (pinfunction "VD_4") (pintype "passive"))
      (node (ref "R16") (pin "1") (pinfunction "1_1") (pintype "passive"))
    )
    (net (code "31") (name "Net-(IC6-+IN)") (class "Default")
      (node (ref "C43") (pin "2") (pinfunction "2_2") (pintype "passive"))
      (node (ref "C45") (pin "2") (pinfunction "2_2") (pintype "passive"))
      (node (ref "IC6") (pin "8") (pinfunction "+IN_8") (pintype "passive"))
      (node (ref "R28") (pin "1") (pinfunction "1_1") (pintype "passive"))
    )
    (net (code "32") (name "Net-(IC6--IN)") (class "Default")
      (node (ref "C43") (pin "1") (pinfunction "1_1") (pintype "passive"))
      (node (ref "C44") (pin "2") (pinfunction "2_2") (pintype "passive"))
      (node (ref "IC6") (pin "1") (pinfunction "-IN_1") (pintype "passive"))
      (node (ref "R29") (pin "1") (pinfunction "1_1") (pintype "passive"))
    )
    (net (code "33") (name "Net-(IC7-+IN)") (class "Default")
      (node (ref "IC7") (pin "3") (pinfunction "+IN_3") (pintype "input"))
      (node (ref "R33") (pin "1") (pinfunction "1_1") (pintype "passive"))
    )
    (net (code "34") (name "Net-(LED1-K)") (class "Default")
      (node (ref "LED1") (pin "1") (pinfunction "K_1") (pintype "passive"))
      (node (ref "R1") (pin "1") (pinfunction "1_1") (pintype "passive"))
    )
    (net (code "35") (name "Net-(M1-G)") (class "Default")
      (node (ref "M1") (pin "4") (pinfunction "G_4") (pintype "passive"))
      (node (ref "R13") (pin "1") (pinfunction "1_1") (pintype "passive"))
      (node (ref "R6") (pin "2") (pinfunction "2_2") (pintype "passive"))
      (node (ref "TP2") (pin "1") (pinfunction "TP_1") (pintype "passive"))
    )
    (net (code "36") (name "Net-(M2-G)") (class "Default")
      (node (ref "M2") (pin "4") (pinfunction "G_4") (pintype "passive"))
      (node (ref "R12") (pin "1") (pinfunction "1_1") (pintype "passive"))
      (node (ref "R5") (pin "2") (pinfunction "2_2") (pintype "passive"))
      (node (ref "TP1") (pin "1") (pinfunction "TP_1") (pintype "passive"))
    )
    (net (code "37") (name "Net-(M3-G)") (class "Default")
      (node (ref "M3") (pin "4") (pinfunction "G_4") (pintype "passive"))
      (node (ref "R18") (pin "2") (pinfunction "2_2") (pintype "passive"))
      (node (ref "R22") (pin "1") (pinfunction "1_1") (pintype "passive"))
      (node (ref "TP6") (pin "1") (pinfunction "TP_1") (pintype "passive"))
    )
    (net (code "38") (name "Net-(M4-G)") (class "Default")
      (node (ref "M4") (pin "4") (pinfunction "G_4") (pintype "passive"))
      (node (ref "R17") (pin "2") (pinfunction "2_2") (pintype "passive"))
      (node (ref "R21") (pin "1") (pinfunction "1_1") (pintype "passive"))
      (node (ref "TP5") (pin "1") (pinfunction "TP_1") (pintype "passive"))
    )
    (net (code "39") (name "unconnected-(IC6-NC_1-Pad3)") (class "Default")
      (node (ref "IC6") (pin "3") (pinfunction "NC_1_3") (pintype "passive+no_connect"))
    )
    (net (code "40") (name "unconnected-(IC6-NC_2-Pad4)") (class "Default")
      (node (ref "IC6") (pin "4") (pinfunction "NC_2_4") (pintype "passive+no_connect"))
    )
    (net (code "41") (name "unconnected-(IC6-NC_3-Pad7)") (class "Default")
      (node (ref "IC6") (pin "7") (pinfunction "NC_3_7") (pintype "passive+no_connect"))
    )
    (net (code "42") (name "unconnected-(J1-Pad1)") (class "Default")
      (node (ref "J1") (pin "1") (pinfunction "1_1") (pintype "passive+no_connect"))
    )
    (net (code "43") (name "unconnected-(J1-Pad2)") (class "Default")
      (node (ref "J1") (pin "2") (pinfunction "2_2") (pintype "passive+no_connect"))
    )
    (net (code "44") (name "unconnected-(J1-Pad3)") (class "Default")
      (node (ref "J1") (pin "3") (pinfunction "3_3") (pintype "passive+no_connect"))
    )
    (net (code "45") (name "unconnected-(J1-Pad4)") (class "Default")
      (node (ref "J1") (pin "4") (pinfunction "4_4") (pintype "passive+no_connect"))
    )
    (net (code "46") (name "unconnected-(J1-Pad5)") (class "Default")
      (node (ref "J1") (pin "5") (pinfunction "5_5") (pintype "passive+no_connect"))
    )
    (net (code "47") (name "unconnected-(J1-Pad6)") (class "Default")
      (node (ref "J1") (pin "6") (pinfunction "6_6") (pintype "passive+no_connect"))
    )
    (net (code "48") (name "unconnected-(J1-Pad7)") (class "Default")
      (node (ref "J1") (pin "7") (pinfunction "7_7") (pintype "passive+no_connect"))
    )
    (net (code "49") (name "unconnected-(J1-Pad10)") (class "Default")
      (node (ref "J1") (pin "10") (pinfunction "10_10") (pintype "passive+no_connect"))
    )
    (net (code "50") (name "unconnected-(J2-Pad2)") (class "Default")
      (node (ref "J2") (pin "2") (pinfunction "2_2") (pintype "passive+no_connect"))
    )
    (net (code "51") (name "unconnected-(J2-Pad5)") (class "Default")
      (node (ref "J2") (pin "5") (pinfunction "5_5") (pintype "passive+no_connect"))
    )
    (net (code "52") (name "unconnected-(J2-Pad6)") (class "Default")
      (node (ref "J2") (pin "6") (pinfunction "6_6") (pintype "passive+no_connect"))
    )
    (net (code "53") (name "unconnected-(J2-Pad7)") (class "Default")
      (node (ref "J2") (pin "7") (pinfunction "7_7") (pintype "passive+no_connect"))
    )
    (net (code "54") (name "unconnected-(J2-Pad8)") (class "Default")
      (node (ref "J2") (pin "8") (pinfunction "8_8") (pintype "passive+no_connect"))
    )
    (net (code "55") (name "unconnected-(J2-Pad9)") (class "Default")
      (node (ref "J2") (pin "9") (pinfunction "9_9") (pintype "passive+no_connect"))
    )
    (net (code "56") (name "unconnected-(J2-Pad10)") (class "Default")
      (node (ref "J2") (pin "10") (pinfunction "10_10") (pintype "passive+no_connect"))
    )
    (net (code "57") (name "unconnected-(M5-Pad1)") (class "Default")
      (node (ref "M5") (pin "1") (pinfunction "1_1") (pintype "passive+no_connect"))
    )
    (net (code "58") (name "unconnected-(M6-Pad1)") (class "Default")
      (node (ref "M6") (pin "1") (pinfunction "1_1") (pintype "passive+no_connect"))
    )
    (net (code "59") (name "unconnected-(M7-Pad1)") (class "Default")
      (node (ref "M7") (pin "1") (pinfunction "1_1") (pintype "passive+no_connect"))
    )
    (net (code "60") (name "unconnected-(M8-Pad1)") (class "Default")
      (node (ref "M8") (pin "1") (pinfunction "1_1") (pintype "passive+no_connect"))
    )
    (net (code "61") (name "unconnected-(R37-Pad3)") (class "Default")
      (node (ref "R37") (pin "3") (pinfunction "3_3") (pintype "passive+no_connect"))
    )
  )
)
